# controller_board.net
KiCad netlist of a schematic drawn in EAGLE
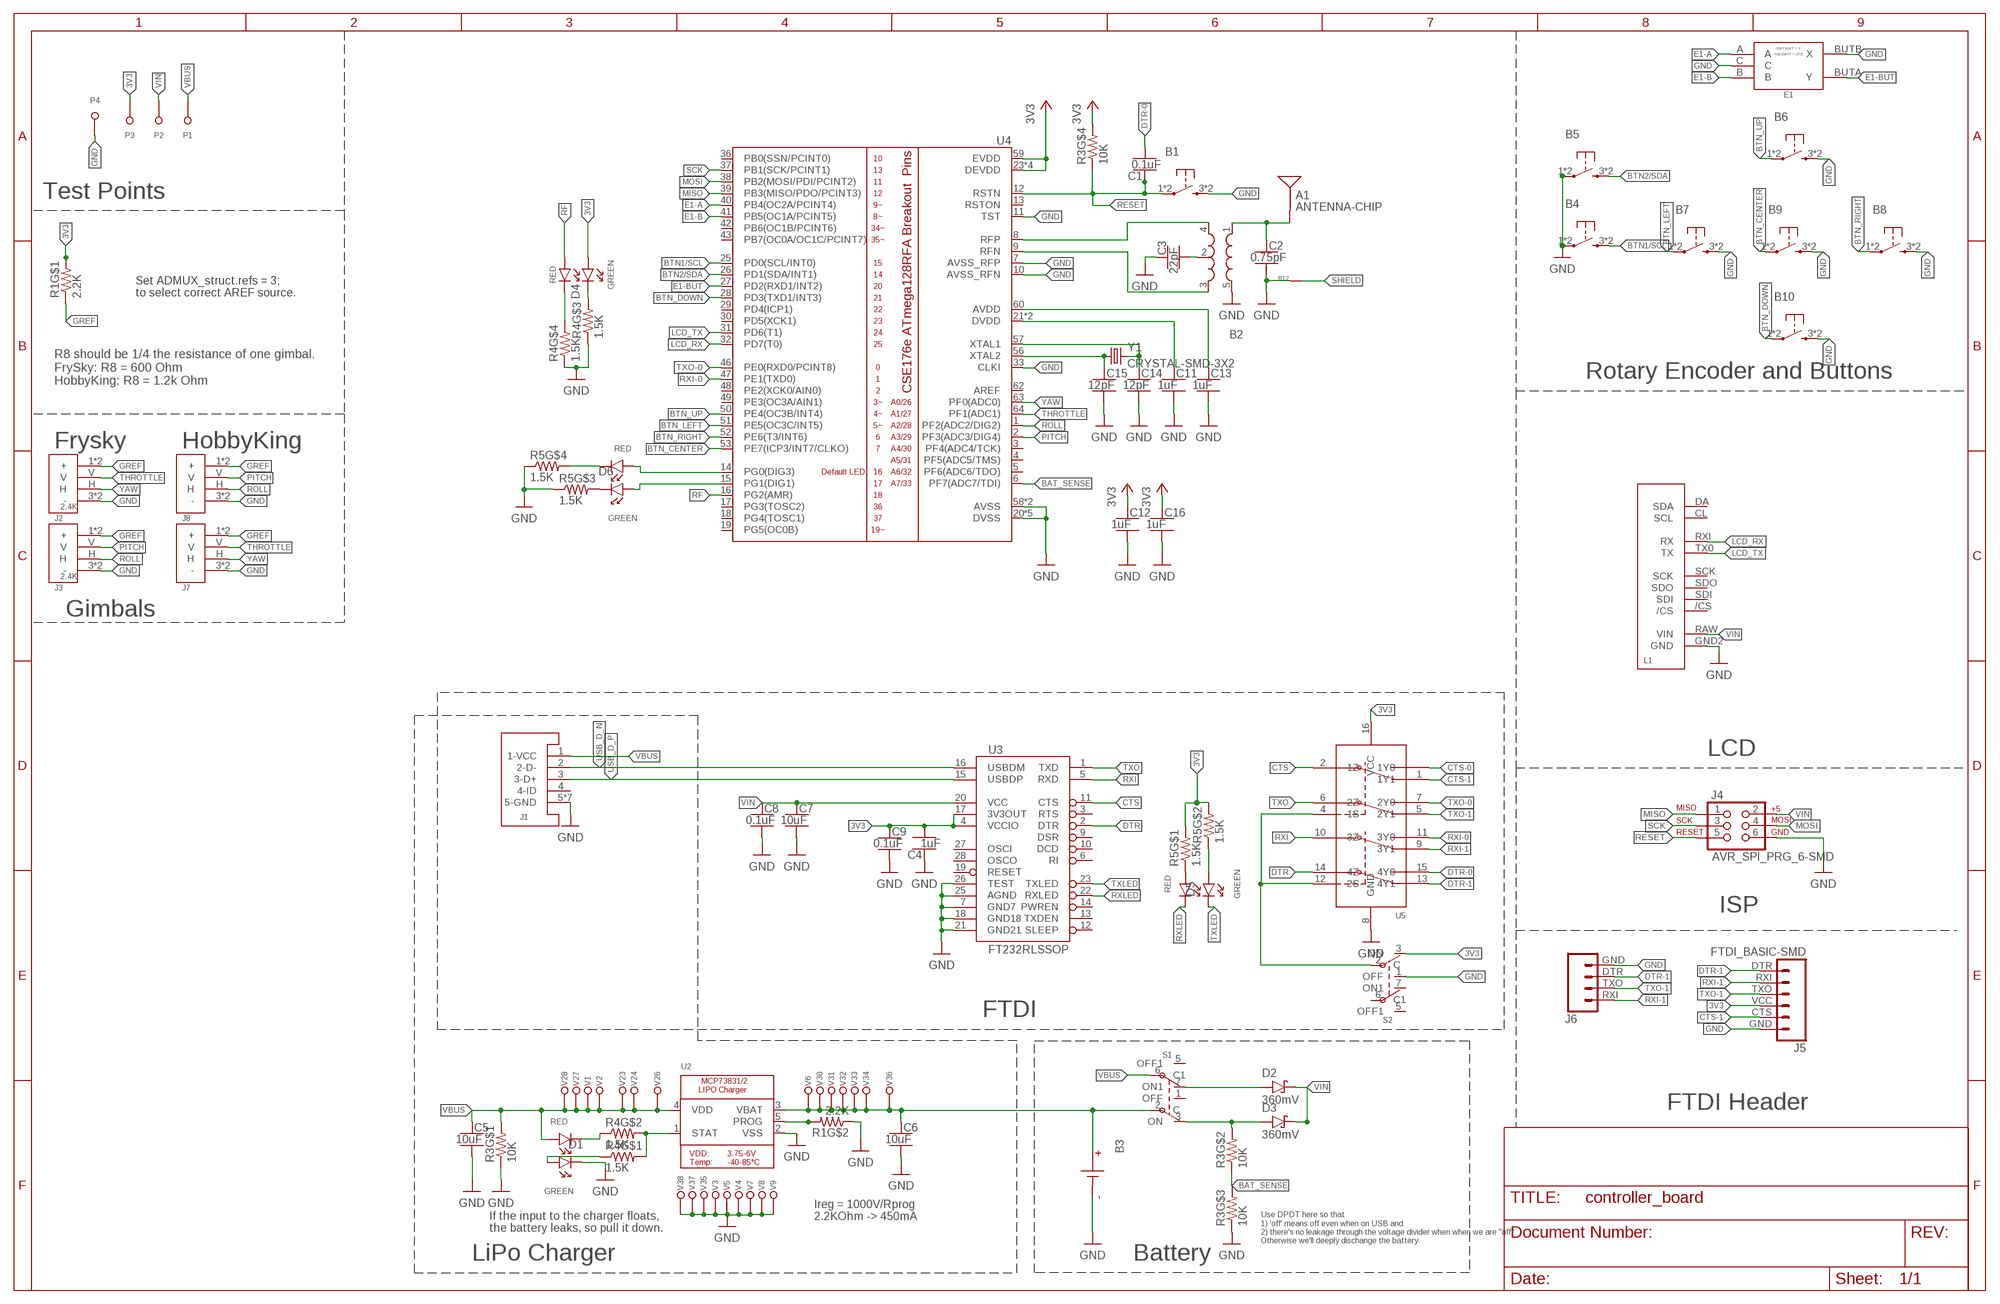
[diagram p0: schematic, sheet 1]

(export (version "E")
  (design (tool "Eeschema 10.0.6"))
  (components
    (comp (ref "A1")
      (value "ANTENNA-CHIP")
      (footprint "eagle-import:ANTENNA-CHIP")
      (fields (field (name "MFR") "Linx Technologies Inc.") (field (name "MPN") "ANT-2.45-CHP-T"))
      (libsource (lib "eagle-import") (part "ANTENNA-CHIP"))
    )
    (comp (ref "B1")
      (value "PUSHBUTTON_-4.5X4.5")
      (footprint "eagle-import:4.5MM_TACTILE_SWITCH_TL3305AF160QG")
      (fields (field (name "MFR") "E-Switch") (field (name "MPN") "TL3305AF160QG"))
      (libsource (lib "eagle-import") (part "PUSHBUTTON_-4.5X4.5"))
    )
    (comp (ref "B2")
      (value "BALUN0805")
      (footprint "eagle-import:BALUN")
      (fields (field (name "MFR") "Wurth Electronics Inc.") (field (name "MPN") "748421245"))
      (libsource (lib "eagle-import") (part "BALUN0805"))
    )
    (comp (ref "B3")
      (value "BATTERY-SMD")
      (footprint "eagle-import:MOLEX-BATTERY-CONNECTOR-SMD-51005-2P")
      (fields (field (name "MFR") "UNKNOWN"))
      (libsource (lib "eagle-import") (part "BATTERY-SMD"))
    )
    (comp (ref "B4")
      (value "PUSHBUTTON_-4.5X4.5")
      (footprint "eagle-import:4.5MM_TACTILE_SWITCH_TL3305AF160QG")
      (fields (field (name "MFR") "E-Switch") (field (name "MPN") "TL3305AF160QG"))
      (libsource (lib "eagle-import") (part "PUSHBUTTON_-4.5X4.5"))
    )
    (comp (ref "B5")
      (value "PUSHBUTTON_-4.5X4.5")
      (footprint "eagle-import:4.5MM_TACTILE_SWITCH_TL3305AF160QG")
      (fields (field (name "MFR") "E-Switch") (field (name "MPN") "TL3305AF160QG"))
      (libsource (lib "eagle-import") (part "PUSHBUTTON_-4.5X4.5"))
    )
    (comp (ref "B6")
      (value "PUSHBUTTON_-4.5X4.5")
      (footprint "eagle-import:4.5MM_TACTILE_SWITCH_TL3305AF160QG")
      (fields (field (name "MFR") "E-Switch") (field (name "MPN") "TL3305AF160QG"))
      (libsource (lib "eagle-import") (part "PUSHBUTTON_-4.5X4.5"))
    )
    (comp (ref "B7")
      (value "PUSHBUTTON_-4.5X4.5")
      (footprint "eagle-import:4.5MM_TACTILE_SWITCH_TL3305AF160QG")
      (fields (field (name "MFR") "E-Switch") (field (name "MPN") "TL3305AF160QG"))
      (libsource (lib "eagle-import") (part "PUSHBUTTON_-4.5X4.5"))
    )
    (comp (ref "B8")
      (value "PUSHBUTTON_-4.5X4.5")
      (footprint "eagle-import:4.5MM_TACTILE_SWITCH_TL3305AF160QG")
      (fields (field (name "MFR") "E-Switch") (field (name "MPN") "TL3305AF160QG"))
      (libsource (lib "eagle-import") (part "PUSHBUTTON_-4.5X4.5"))
    )
    (comp (ref "B9")
      (value "PUSHBUTTON_-4.5X4.5")
      (footprint "eagle-import:4.5MM_TACTILE_SWITCH_TL3305AF160QG")
      (fields (field (name "MFR") "E-Switch") (field (name "MPN") "TL3305AF160QG"))
      (libsource (lib "eagle-import") (part "PUSHBUTTON_-4.5X4.5"))
    )
    (comp (ref "B10")
      (value "PUSHBUTTON_-4.5X4.5")
      (footprint "eagle-import:4.5MM_TACTILE_SWITCH_TL3305AF160QG")
      (fields (field (name "MFR") "E-Switch") (field (name "MPN") "TL3305AF160QG"))
      (libsource (lib "eagle-import") (part "PUSHBUTTON_-4.5X4.5"))
    )
    (comp (ref "B12")
      (value "NET_BRIDGE")
      (footprint "eagle-import:NET_BRIDGE")
      (libsource (lib "eagle-import") (part "NET_BRIDGE"))
    )
    (comp (ref "C1")
      (value "0.1uF")
      (footprint "eagle-import:CAPC1608X100")
      (fields (field (name "MFR") "KEMET") (field (name "MPN") "C0603C104K8RACTU"))
      (libsource (lib "eagle-import") (part "CAPACITOR-NP_SMD-0603_CERAMIC-0.1UF"))
    )
    (comp (ref "C2")
      (value "0.75pF")
      (footprint "eagle-import:CAPC1608X100")
      (fields (field (name "MFR") "Yageo") (field (name "MPN") "CC0603BRNPO9BNR75"))
      (libsource (lib "eagle-import") (part "CAPACITOR-NP_SMD-0603_CERAMIC-0.75PF"))
    )
    (comp (ref "C3")
      (value "22pF")
      (footprint "eagle-import:CAPC1608X100")
      (fields (field (name "MFR") "AVX Corporation") (field (name "MPN") "06036A220KAT2A"))
      (libsource (lib "eagle-import") (part "CAPACITOR-NP_SMD-0603_CERAMIC-22PF"))
    )
    (comp (ref "C4")
      (value "1uF")
      (footprint "eagle-import:CAPC1608X100")
      (fields (field (name "MFR") "Samsung Electro-Mechanics") (field (name "MPN") "CL10A105KP8NNNC"))
      (libsource (lib "eagle-import") (part "CAPACITOR-NP_SMD-0603_CERAMIC-1UF"))
    )
    (comp (ref "C5")
      (value "10uF")
      (footprint "eagle-import:CAPC1608X100")
      (fields (field (name "MFR") "Samsung Electro-Mechanics") (field (name "MPN") "CL10A106MQ8NNNC"))
      (libsource (lib "eagle-import") (part "CAPACITOR-NP_SMD-0603_CERAMIC-10UF"))
    )
    (comp (ref "C6")
      (value "10uF")
      (footprint "eagle-import:CAPC1608X100")
      (fields (field (name "MFR") "Samsung Electro-Mechanics") (field (name "MPN") "CL10A106MQ8NNNC"))
      (libsource (lib "eagle-import") (part "CAPACITOR-NP_SMD-0603_CERAMIC-10UF"))
    )
    (comp (ref "C7")
      (value "10uF")
      (footprint "eagle-import:CAPC1608X100")
      (fields (field (name "MFR") "Samsung Electro-Mechanics") (field (name "MPN") "CL10A106MQ8NNNC"))
      (libsource (lib "eagle-import") (part "CAPACITOR-NP_SMD-0603_CERAMIC-10UF"))
    )
    (comp (ref "C8")
      (value "0.1uF")
      (footprint "eagle-import:CAPC1608X100")
      (fields (field (name "MFR") "KEMET") (field (name "MPN") "C0603C104K8RACTU"))
      (libsource (lib "eagle-import") (part "CAPACITOR-NP_SMD-0603_CERAMIC-0.1UF"))
    )
    (comp (ref "C9")
      (value "0.1uF")
      (footprint "eagle-import:CAPC1608X100")
      (fields (field (name "MFR") "KEMET") (field (name "MPN") "C0603C104K8RACTU"))
      (libsource (lib "eagle-import") (part "CAPACITOR-NP_SMD-0603_CERAMIC-0.1UF"))
    )
    (comp (ref "C11")
      (value "1uF")
      (footprint "eagle-import:CAPC1608X100")
      (fields (field (name "MFR") "Samsung Electro-Mechanics") (field (name "MPN") "CL10A105KP8NNNC"))
      (libsource (lib "eagle-import") (part "CAPACITOR-NP_SMD-0603_CERAMIC-1UF"))
    )
    (comp (ref "C12")
      (value "1uF")
      (footprint "eagle-import:CAPC1608X100")
      (fields (field (name "MFR") "Samsung Electro-Mechanics") (field (name "MPN") "CL10A105KP8NNNC"))
      (libsource (lib "eagle-import") (part "CAPACITOR-NP_SMD-0603_CERAMIC-1UF"))
    )
    (comp (ref "C13")
      (value "1uF")
      (footprint "eagle-import:CAPC1608X100")
      (fields (field (name "MFR") "Samsung Electro-Mechanics") (field (name "MPN") "CL10A105KP8NNNC"))
      (libsource (lib "eagle-import") (part "CAPACITOR-NP_SMD-0603_CERAMIC-1UF"))
    )
    (comp (ref "C14")
      (value "12pF")
      (footprint "eagle-import:CAPC1608X100")
      (fields (field (name "MFR") "Vishay Vitramon") (field (name "MPN") "VJ0603A120FXQCW1BC"))
      (libsource (lib "eagle-import") (part "CAPACITOR-NP_SMD-0603_CERAMIC-12PF"))
    )
    (comp (ref "C15")
      (value "12pF")
      (footprint "eagle-import:CAPC1608X100")
      (fields (field (name "MFR") "Vishay Vitramon") (field (name "MPN") "VJ0603A120FXQCW1BC"))
      (libsource (lib "eagle-import") (part "CAPACITOR-NP_SMD-0603_CERAMIC-12PF"))
    )
    (comp (ref "C16")
      (value "1uF")
      (footprint "eagle-import:CAPC1608X100")
      (fields (field (name "MFR") "Samsung Electro-Mechanics") (field (name "MPN") "CL10A105KP8NNNC"))
      (libsource (lib "eagle-import") (part "CAPACITOR-NP_SMD-0603_CERAMIC-1UF"))
    )
    (comp (ref "D1")
      (value "LED-2X-GREEN/RED-1.6X1.5MM")
      (footprint "eagle-import:LED-2X-LITE-ON-1.6MMX1.5MM")
      (fields
        (field (name "COLOR2") "GREEN")
        (field (name "COLOR1") "RED")
        (field (name "MFR") "Lite-On Inc.")
        (field (name "MPN") "LTST-C195TGKRKT")
      )
      (libsource (lib "eagle-import") (part "LED-2X-GREEN/RED-1.6X1.5MM"))
    )
    (comp (ref "D2")
      (value "360mV")
      (footprint "eagle-import:SODFL3516X96")
      (fields
        (field (name "MFR") "Toshiba Semiconductor and Storage")
        (field (name "MPN") "CRS08(TE85L,Q,M)")
      )
      (libsource (lib "eagle-import") (part "DIODE-SCHOTTKY_-SMD-SOD123"))
    )
    (comp (ref "D3")
      (value "360mV")
      (footprint "eagle-import:SODFL3516X96")
      (fields
        (field (name "MFR") "Toshiba Semiconductor and Storage")
        (field (name "MPN") "CRS08(TE85L,Q,M)")
      )
      (libsource (lib "eagle-import") (part "DIODE-SCHOTTKY_-SMD-SOD123"))
    )
    (comp (ref "D4")
      (value "LED-2X-GREEN/RED-1.6X1.5MM")
      (footprint "eagle-import:LED-2X-LITE-ON-1.6MMX1.5MM")
      (fields
        (field (name "COLOR2") "GREEN")
        (field (name "COLOR1") "RED")
        (field (name "MFR") "Lite-On Inc.")
        (field (name "MPN") "LTST-C195TGKRKT")
      )
      (libsource (lib "eagle-import") (part "LED-2X-GREEN/RED-1.6X1.5MM"))
    )
    (comp (ref "D5")
      (value "LED-2X-GREEN/RED-1.6X1.5MM")
      (footprint "eagle-import:LED-2X-LITE-ON-1.6MMX1.5MM")
      (fields
        (field (name "COLOR2") "GREEN")
        (field (name "COLOR1") "RED")
        (field (name "MFR") "Lite-On Inc.")
        (field (name "MPN") "LTST-C195TGKRKT")
      )
      (libsource (lib "eagle-import") (part "LED-2X-GREEN/RED-1.6X1.5MM"))
    )
    (comp (ref "D6")
      (value "LED-2X-GREEN/RED-1.6X1.5MM")
      (footprint "eagle-import:LED-2X-LITE-ON-1.6MMX1.5MM")
      (fields
        (field (name "COLOR2") "GREEN")
        (field (name "COLOR1") "RED")
        (field (name "MFR") "Lite-On Inc.")
        (field (name "MPN") "LTST-C195TGKRKT")
      )
      (libsource (lib "eagle-import") (part "LED-2X-GREEN/RED-1.6X1.5MM"))
    )
    (comp (ref "E1")
      (value "ROTARY-ENCODER-W/BUTTON-BOURNS-PEC12R-4217F")
      (footprint "eagle-import:BOURNS-PEC12R")
      (fields (field (name "DETENT") "Y") (field (name "HEIGHT") "17.5"))
      (libsource (lib "eagle-import") (part "ROTARY-ENCODER-W/BUTTON-BOURNS-PEC12R-4217F"))
    )
    (comp (ref "J1")
      (value "USB-MICROA-AMPHENOL-10118192-0001LF")
      (footprint "eagle-import:USB-MICROA-10118192-0001LF")
      (libsource (lib "eagle-import") (part "USB-MICROA-AMPHENOL-10118192-0001LF"))
    )
    (comp (ref "J2")
      (value "2.4K")
      (footprint "eagle-import:JST-13-PTH")
      (fields (field (name "MFR") "TE Connectivity AMP Connectors") (field (name "MPN") "1-1735446-2"))
      (libsource (lib "eagle-import") (part "FRSKY-GIMBAL-FRYSKY"))
    )
    (comp (ref "J3")
      (value "2.4K")
      (footprint "eagle-import:JST-13-PTH")
      (fields
        (field (name "MFR") "TE Connectivity AMP Connectors")
        (field (name "MPN") "1-1735446-2")
        (field (name "SPICEPREFIX") "E")
      )
      (libsource (lib "eagle-import") (part "FRSKY-GIMBAL-FRYSKY"))
    )
    (comp (ref "J4")
      (value "AVR_SPI_PRG_6-SMD")
      (footprint "eagle-import:2X3-SMD")
      (fields (field (name "MFR") "Amphenol ICC (FCI)") (field (name "MPN") "95278-101A06LF"))
      (libsource (lib "eagle-import") (part "AVR_SPI_PRG_6-SMD"))
    )
    (comp (ref "J5")
      (value "FTDI_BASIC-SMD")
      (footprint "eagle-import:FTDI-BASIC-SMD")
      (fields (field (name "MFR") "Harwin Inc.") (field (name "MPN") "M20-8890645"))
      (libsource (lib "eagle-import") (part "FTDI_BASIC-SMD"))
    )
    (comp (ref "J6")
      (value "FTDI-4PIN-RIGHT-ANGLE-SMD")
      (footprint "eagle-import:HEADER-2X2-0.1IN-MALE-RIGHT-ANGLE-SMD")
      (libsource (lib "eagle-import") (part "FTDI-4PIN-RIGHT-ANGLE-SMD"))
    )
    (comp (ref "J7")
      (value "FRSKY-GIMBAL-2X-SERVO-SMD")
      (footprint "eagle-import:2X-SERVO-SMD")
      (fields (field (name "MFR") "Harwin Inc.") (field (name "MPN") "M20-8890645"))
      (libsource (lib "eagle-import") (part "FRSKY-GIMBAL-2X-SERVO-SMD"))
    )
    (comp (ref "J8")
      (value "FRSKY-GIMBAL-2X-SERVO-SMD")
      (footprint "eagle-import:2X-SERVO-SMD")
      (fields (field (name "MFR") "Harwin Inc.") (field (name "MPN") "M20-8890645"))
      (libsource (lib "eagle-import") (part "FRSKY-GIMBAL-2X-SERVO-SMD"))
    )
    (comp (ref "L1")
      (value "SPARKFUN_SERLCD_SERIAL_REDUCED-SMD")
      (footprint "eagle-import:SPARKFUN_SERLCD_16X2_REDUCED_SMD")
      (libsource (lib "eagle-import") (part "SPARKFUN_SERLCD_SERIAL_REDUCED-SMD"))
    )
    (comp (ref "P1")
      (value "TEST-POINT")
      (footprint "eagle-import:TEST-POINT-KEYSTONE-5000")
      (fields (field (name "MFR") "Keystone Electronics") (field (name "MPN") "5001"))
      (libsource (lib "eagle-import") (part "TEST-POINT"))
    )
    (comp (ref "P2")
      (value "TEST-POINT")
      (footprint "eagle-import:TEST-POINT-KEYSTONE-5000")
      (fields (field (name "MFR") "Keystone Electronics") (field (name "MPN") "5001"))
      (libsource (lib "eagle-import") (part "TEST-POINT"))
    )
    (comp (ref "P3")
      (value "TEST-POINT")
      (footprint "eagle-import:TEST-POINT-KEYSTONE-5000")
      (fields (field (name "MFR") "Keystone Electronics") (field (name "MPN") "5001"))
      (libsource (lib "eagle-import") (part "TEST-POINT"))
    )
    (comp (ref "P4")
      (value "TEST-POINT")
      (footprint "eagle-import:TEST-POINT-KEYSTONE-5000")
      (fields (field (name "MFR") "Keystone Electronics") (field (name "MPN") "5001"))
      (libsource (lib "eagle-import") (part "TEST-POINT"))
    )
    (comp (ref "R1")
      (value "2.2K")
      (footprint "eagle-import:RESCAXS50P200X100X45-8")
      (libsource (lib "eagle-import") (part "RESISTOR-PACK-4X-2.2K"))
    )
    (comp (ref "R3")
      (value "10K")
      (footprint "eagle-import:RESCAXS50P200X100X45-8")
      (fields (field (name "MFR") "Panasonic Electronic Components") (field (name "MPN") "EXB-N8V103JX"))
      (libsource (lib "eagle-import") (part "RESISTOR-PACK-4X-10K"))
    )
    (comp (ref "R4")
      (value "1.5K")
      (footprint "eagle-import:RESCAXS50P200X100X45-8")
      (libsource (lib "eagle-import") (part "RESISTOR-PACK-4X-1.5K"))
    )
    (comp (ref "R5")
      (value "1.5K")
      (footprint "eagle-import:RESCAXS50P200X100X45-8")
      (libsource (lib "eagle-import") (part "RESISTOR-PACK-4X-1.5K"))
    )
    (comp (ref "S1")
      (value "SWITCH-DPDT-300MA-6V-SMD")
      (footprint "eagle-import:JS202011JCQN")
      (libsource (lib "eagle-import") (part "SWITCH-DPDT-300MA-6V-SMD"))
    )
    (comp (ref "S2")
      (value "SWITCH-DPDT-300MA-6V-SMD")
      (footprint "eagle-import:JS202011JCQN")
      (libsource (lib "eagle-import") (part "SWITCH-DPDT-300MA-6V-SMD"))
    )
    (comp (ref "U2")
      (value "MCP73831T-2ACI/OT")
      (footprint "eagle-import:SOT23-5")
      (fields (field (name "MFR") "Microchip Technology"))
      (libsource (lib "eagle-import") (part "MCP73831/2"))
    )
    (comp (ref "U3")
      (value "FT232RLSSOP")
      (footprint "eagle-import:SSOP28DB")
      (libsource (lib "eagle-import") (part "FT232RLSSOP"))
    )
    (comp (ref "U4")
      (value "ATMEGA128RFA1")
      (footprint "eagle-import:QFN-64")
      (fields (field (name "MFR") "Microchip Technology") (field (name "MPN") "ATMEGA128RFA1-ZU"))
      (libsource (lib "eagle-import") (part "ATMEGA128RFA1"))
    )
    (comp (ref "U5")
      (value "DPDT-X2")
      (footprint "eagle-import:SOP65P640X110-16")
      (fields (field (name "MFR") "NXP USA Inc.") (field (name "MPN") "NX3L2467PW,118"))
      (libsource (lib "eagle-import") (part "DPDT-X2"))
    )
    (comp (ref "V1")
      (value "LOCKED-VIA-0.2")
      (footprint "eagle-import:VIA-0.2MM")
      (libsource (lib "eagle-import") (part "LOCKED-VIA-0.2"))
    )
    (comp (ref "V2")
      (value "LOCKED-VIA-0.2")
      (footprint "eagle-import:VIA-0.2MM")
      (libsource (lib "eagle-import") (part "LOCKED-VIA-0.2"))
    )
    (comp (ref "V3")
      (value "LOCKED-VIA-0.2")
      (footprint "eagle-import:VIA-0.2MM")
      (libsource (lib "eagle-import") (part "LOCKED-VIA-0.2"))
    )
    (comp (ref "V4")
      (value "LOCKED-VIA-0.2")
      (footprint "eagle-import:VIA-0.2MM")
      (libsource (lib "eagle-import") (part "LOCKED-VIA-0.2"))
    )
    (comp (ref "V5")
      (value "LOCKED-VIA-0.2")
      (footprint "eagle-import:VIA-0.2MM")
      (libsource (lib "eagle-import") (part "LOCKED-VIA-0.2"))
    )
    (comp (ref "V6")
      (value "LOCKED-VIA-0.2")
      (footprint "eagle-import:VIA-0.2MM")
      (libsource (lib "eagle-import") (part "LOCKED-VIA-0.2"))
    )
    (comp (ref "V7")
      (value "LOCKED-VIA-0.2")
      (footprint "eagle-import:VIA-0.2MM")
      (libsource (lib "eagle-import") (part "LOCKED-VIA-0.2"))
    )
    (comp (ref "V8")
      (value "LOCKED-VIA-0.2")
      (footprint "eagle-import:VIA-0.2MM")
      (libsource (lib "eagle-import") (part "LOCKED-VIA-0.2"))
    )
    (comp (ref "V9")
      (value "LOCKED-VIA-0.2")
      (footprint "eagle-import:VIA-0.2MM")
      (libsource (lib "eagle-import") (part "LOCKED-VIA-0.2"))
    )
    (comp (ref "V23")
      (value "LOCKED-VIA-0.2")
      (footprint "eagle-import:VIA-0.2MM")
      (libsource (lib "eagle-import") (part "LOCKED-VIA-0.2"))
    )
    (comp (ref "V24")
      (value "LOCKED-VIA-0.2")
      (footprint "eagle-import:VIA-0.2MM")
      (libsource (lib "eagle-import") (part "LOCKED-VIA-0.2"))
    )
    (comp (ref "V26")
      (value "LOCKED-VIA-0.2")
      (footprint "eagle-import:VIA-0.2MM")
      (libsource (lib "eagle-import") (part "LOCKED-VIA-0.2"))
    )
    (comp (ref "V27")
      (value "LOCKED-VIA-0.2")
      (footprint "eagle-import:VIA-0.2MM")
      (libsource (lib "eagle-import") (part "LOCKED-VIA-0.2"))
    )
    (comp (ref "V28")
      (value "LOCKED-VIA-0.2")
      (footprint "eagle-import:VIA-0.2MM")
      (libsource (lib "eagle-import") (part "LOCKED-VIA-0.2"))
    )
    (comp (ref "V30")
      (value "LOCKED-VIA-0.2")
      (footprint "eagle-import:VIA-0.2MM")
      (libsource (lib "eagle-import") (part "LOCKED-VIA-0.2"))
    )
    (comp (ref "V31")
      (value "LOCKED-VIA-0.2")
      (footprint "eagle-import:VIA-0.2MM")
      (libsource (lib "eagle-import") (part "LOCKED-VIA-0.2"))
    )
    (comp (ref "V32")
      (value "LOCKED-VIA-0.2")
      (footprint "eagle-import:VIA-0.2MM")
      (libsource (lib "eagle-import") (part "LOCKED-VIA-0.2"))
    )
    (comp (ref "V33")
      (value "LOCKED-VIA-0.2")
      (footprint "eagle-import:VIA-0.2MM")
      (libsource (lib "eagle-import") (part "LOCKED-VIA-0.2"))
    )
    (comp (ref "V34")
      (value "LOCKED-VIA-0.2")
      (footprint "eagle-import:VIA-0.2MM")
      (libsource (lib "eagle-import") (part "LOCKED-VIA-0.2"))
    )
    (comp (ref "V35")
      (value "LOCKED-VIA-0.2")
      (footprint "eagle-import:VIA-0.2MM")
      (libsource (lib "eagle-import") (part "LOCKED-VIA-0.2"))
    )
    (comp (ref "V36")
      (value "LOCKED-VIA-0.2")
      (footprint "eagle-import:VIA-0.2MM")
      (libsource (lib "eagle-import") (part "LOCKED-VIA-0.2"))
    )
    (comp (ref "V37")
      (value "LOCKED-VIA-0.2")
      (footprint "eagle-import:VIA-0.2MM")
      (libsource (lib "eagle-import") (part "LOCKED-VIA-0.2"))
    )
    (comp (ref "V38")
      (value "LOCKED-VIA-0.2")
      (footprint "eagle-import:VIA-0.2MM")
      (libsource (lib "eagle-import") (part "LOCKED-VIA-0.2"))
    )
    (comp (ref "Y1")
      (value "CRYSTAL-SMD-3X2")
      (footprint "eagle-import:OSCCC320X250X85")
      (fields (field (name "MFR") "Abracon LLC") (field (name "MPN") "ABM8-16.000MHZ-B2-T"))
      (libsource (lib "eagle-import") (part "CRYSTAL-SMD-3X2"))
    )
  )
  (nets
    (net (code "1") (name "3V3") (class "Default")
      (node (ref "C12") (pin "1") (pinfunction "1_1") (pintype "passive"))
      (node (ref "C16") (pin "1") (pinfunction "1_1") (pintype "passive"))
      (node (ref "C4") (pin "2") (pinfunction "2_2") (pintype "passive"))
      (node (ref "C9") (pin "1") (pinfunction "1_1") (pintype "passive"))
      (node (ref "D4") (pin "A1") (pinfunction "A1_A1") (pintype "passive"))
      (node (ref "J5") (pin "VCC") (pinfunction "4_VCC") (pintype "passive"))
      (node (ref "P3") (pin "T") (pinfunction "T_T") (pintype "bidirectional"))
      (node (ref "R1") (pin "5") (pinfunction "2_5") (pintype "passive"))
      (node (ref "R3") (pin "8") (pinfunction "2_8") (pintype "passive"))
      (node (ref "R5") (pin "5") (pinfunction "2_5") (pintype "passive"))
      (node (ref "R5") (pin "6") (pinfunction "2_6") (pintype "passive"))
      (node (ref "S2") (pin "3") (pinfunction "ON_3") (pintype "bidirectional"))
      (node (ref "U3") (pin "17") (pinfunction "3V3OUT_17") (pintype "output"))
      (node (ref "U3") (pin "4") (pinfunction "VCCIO_4") (pintype "power_in"))
      (node (ref "U4") (pin "23") (pinfunction "DEVDD_23") (pintype "bidirectional"))
      (node (ref "U4") (pin "34") (pinfunction "DEVDD_34") (pintype "bidirectional"))
      (node (ref "U4") (pin "44") (pinfunction "DEVDD_44") (pintype "bidirectional"))
      (node (ref "U4") (pin "54") (pinfunction "DEVDD_54") (pintype "bidirectional"))
      (node (ref "U4") (pin "59") (pinfunction "EVDD_59") (pintype "bidirectional"))
      (node (ref "U5") (pin "16") (pinfunction "VCC_16") (pintype "bidirectional"))
    )
    (net (code "2") (name "BAT_SENSE") (class "Default")
      (node (ref "R3") (pin "3") (pinfunction "1_3") (pintype "passive"))
      (node (ref "R3") (pin "7") (pinfunction "2_7") (pintype "passive"))
      (node (ref "U4") (pin "6") (pinfunction "PF7(ADC7/TDI)_6") (pintype "bidirectional"))
    )
    (net (code "3") (name "BTN1{slash}SCL") (class "Default")
      (node (ref "B4") (pin "3") (pinfunction "2_3") (pintype "passive"))
      (node (ref "B4") (pin "4") (pinfunction "2_4") (pintype "passive"))
      (node (ref "U4") (pin "25") (pinfunction "PD0(SCL/INT0)_25") (pintype "bidirectional"))
    )
    (net (code "4") (name "BTN2{slash}SDA") (class "Default")
      (node (ref "B5") (pin "3") (pinfunction "2_3") (pintype "passive"))
      (node (ref "B5") (pin "4") (pinfunction "2_4") (pintype "passive"))
      (node (ref "U4") (pin "26") (pinfunction "PD1(SDA/INT1)_26") (pintype "bidirectional"))
    )
    (net (code "5") (name "BTN_CENTER") (class "Default")
      (node (ref "B9") (pin "1") (pinfunction "1_1") (pintype "passive"))
      (node (ref "B9") (pin "2") (pinfunction "1_2") (pintype "passive"))
      (node (ref "U4") (pin "53") (pinfunction "PE7(ICP3/INT7/CLKO)_53") (pintype "bidirectional"))
    )
    (net (code "6") (name "BTN_DOWN") (class "Default")
      (node (ref "B10") (pin "1") (pinfunction "1_1") (pintype "passive"))
      (node (ref "B10") (pin "2") (pinfunction "1_2") (pintype "passive"))
      (node (ref "U4") (pin "28") (pinfunction "PD3(TXD1/INT3)_28") (pintype "bidirectional"))
    )
    (net (code "7") (name "BTN_LEFT") (class "Default")
      (node (ref "B7") (pin "1") (pinfunction "1_1") (pintype "passive"))
      (node (ref "B7") (pin "2") (pinfunction "1_2") (pintype "passive"))
      (node (ref "U4") (pin "51") (pinfunction "PE5(OC3C/INT5)_51") (pintype "bidirectional"))
    )
    (net (code "8") (name "BTN_RIGHT") (class "Default")
      (node (ref "B8") (pin "1") (pinfunction "1_1") (pintype "passive"))
      (node (ref "B8") (pin "2") (pinfunction "1_2") (pintype "passive"))
      (node (ref "U4") (pin "52") (pinfunction "PE6(T3/INT6)_52") (pintype "bidirectional"))
    )
    (net (code "9") (name "BTN_UP") (class "Default")
      (node (ref "B6") (pin "1") (pinfunction "1_1") (pintype "passive"))
      (node (ref "B6") (pin "2") (pinfunction "1_2") (pintype "passive"))
      (node (ref "U4") (pin "50") (pinfunction "PE4(OC3B/INT4)_50") (pintype "bidirectional"))
    )
    (net (code "10") (name "CTS") (class "Default")
      (node (ref "U3") (pin "11") (pinfunction "CTS_11") (pintype "input"))
      (node (ref "U5") (pin "2") (pinfunction "1Z_2") (pintype "bidirectional"))
    )
    (net (code "11") (name "CTS-0") (class "Default")
      (node (ref "U5") (pin "3") (pinfunction "1Y0_3") (pintype "bidirectional"))
    )
    (net (code "12") (name "CTS-1") (class "Default")
      (node (ref "J5") (pin "CTS") (pinfunction "5_CTS") (pintype "passive"))
      (node (ref "U5") (pin "1") (pinfunction "1Y1_1") (pintype "bidirectional"))
    )
    (net (code "13") (name "DTR") (class "Default")
      (node (ref "U3") (pin "2") (pinfunction "DTR_2") (pintype "output"))
      (node (ref "U5") (pin "14") (pinfunction "4Z_14") (pintype "bidirectional"))
    )
    (net (code "14") (name "DTR-0") (class "Default")
      (node (ref "C1") (pin "2") (pinfunction "2_2") (pintype "passive"))
      (node (ref "U5") (pin "15") (pinfunction "4Y0_15") (pintype "bidirectional"))
    )
    (net (code "15") (name "DTR-1") (class "Default")
      (node (ref "J5") (pin "DTR") (pinfunction "1_DTR") (pintype "passive"))
      (node (ref "J6") (pin "DTR") (pinfunction "3_DTR") (pintype "bidirectional"))
      (node (ref "U5") (pin "13") (pinfunction "4Y1_13") (pintype "bidirectional"))
    )
    (net (code "16") (name "E1-A") (class "Default")
      (node (ref "E1") (pin "A") (pinfunction "A_A") (pintype "bidirectional"))
      (node (ref "U4") (pin "40") (pinfunction "PB4(OC2A/PCINT4)_40") (pintype "bidirectional"))
    )
    (net (code "17") (name "E1-B") (class "Default")
      (node (ref "E1") (pin "B") (pinfunction "B_B") (pintype "bidirectional"))
      (node (ref "U4") (pin "41") (pinfunction "PB5(OC1A/PCINT5)_41") (pintype "bidirectional"))
    )
    (net (code "18") (name "E1-BUT") (class "Default")
      (node (ref "E1") (pin "BUTA") (pinfunction "Y_BUTA") (pintype "bidirectional"))
      (node (ref "U4") (pin "27") (pinfunction "PD2(RXD1/INT2)_27") (pintype "bidirectional"))
    )
    (net (code "19") (name "GND") (class "Default")
      (node (ref "B1") (pin "3") (pinfunction "2_3") (pintype "passive"))
      (node (ref "B1") (pin "4") (pinfunction "2_4") (pintype "passive"))
      (node (ref "B10") (pin "3") (pinfunction "2_3") (pintype "passive"))
      (node (ref "B10") (pin "4") (pinfunction "2_4") (pintype "passive"))
      (node (ref "B12") (pin "P1") (pinfunction "P1_P1") (pintype "bidirectional"))
      (node (ref "B2") (pin "5") (pinfunction "GND_5") (pintype "bidirectional"))
      (node (ref "B3") (pin "G") (pinfunction "N_G") (pintype "bidirectional"))
      (node (ref "B3") (pin "G2") (pinfunction "N_G2") (pintype "bidirectional"))
      (node (ref "B3") (pin "G3") (pinfunction "N_G3") (pintype "bidirectional"))
      (node (ref "B4") (pin "1") (pinfunction "1_1") (pintype "passive"))
      (node (ref "B4") (pin "2") (pinfunction "1_2") (pintype "passive"))
      (node (ref "B5") (pin "1") (pinfunction "1_1") (pintype "passive"))
      (node (ref "B5") (pin "2") (pinfunction "1_2") (pintype "passive"))
      (node (ref "B6") (pin "3") (pinfunction "2_3") (pintype "passive"))
      (node (ref "B6") (pin "4") (pinfunction "2_4") (pintype "passive"))
      (node (ref "B7") (pin "3") (pinfunction "2_3") (pintype "passive"))
      (node (ref "B7") (pin "4") (pinfunction "2_4") (pintype "passive"))
      (node (ref "B8") (pin "3") (pinfunction "2_3") (pintype "passive"))
      (node (ref "B8") (pin "4") (pinfunction "2_4") (pintype "passive"))
      (node (ref "B9") (pin "3") (pinfunction "2_3") (pintype "passive"))
      (node (ref "B9") (pin "4") (pinfunction "2_4") (pintype "passive"))
      (node (ref "C11") (pin "2") (pinfunction "2_2") (pintype "passive"))
      (node (ref "C12") (pin "2") (pinfunction "2_2") (pintype "passive"))
      (node (ref "C13") (pin "2") (pinfunction "2_2") (pintype "passive"))
      (node (ref "C14") (pin "2") (pinfunction "2_2") (pintype "passive"))
      (node (ref "C15") (pin "2") (pinfunction "2_2") (pintype "passive"))
      (node (ref "C16") (pin "2") (pinfunction "2_2") (pintype "passive"))
      (node (ref "C2") (pin "2") (pinfunction "2_2") (pintype "passive"))
      (node (ref "C3") (pin "1") (pinfunction "1_1") (pintype "passive"))
      (node (ref "C4") (pin "1") (pinfunction "1_1") (pintype "passive"))
      (node (ref "C5") (pin "2") (pinfunction "2_2") (pintype "passive"))
      (node (ref "C6") (pin "2") (pinfunction "2_2") (pintype "passive"))
      (node (ref "C7") (pin "2") (pinfunction "2_2") (pintype "passive"))
      (node (ref "C8") (pin "2") (pinfunction "2_2") (pintype "passive"))
      (node (ref "C9") (pin "2") (pinfunction "2_2") (pintype "passive"))
      (node (ref "D1") (pin "C1") (pinfunction "C1_C1") (pintype "passive"))
      (node (ref "E1") (pin "BUTB") (pinfunction "X_BUTB") (pintype "bidirectional"))
      (node (ref "E1") (pin "C") (pinfunction "C_C") (pintype "bidirectional"))
      (node (ref "J1") (pin "10") (pinfunction "5-GND_10") (pintype "bidirectional"))
      (node (ref "J1") (pin "11") (pinfunction "5-GND_11") (pintype "bidirectional"))
      (node (ref "J1") (pin "5") (pinfunction "5-GND_5") (pintype "bidirectional"))
      (node (ref "J1") (pin "6") (pinfunction "5-GND_6") (pintype "bidirectional"))
      (node (ref "J1") (pin "7") (pinfunction "5-GND_7") (pintype "bidirectional"))
      (node (ref "J1") (pin "8") (pinfunction "5-GND_8") (pintype "bidirectional"))
      (node (ref "J1") (pin "9") (pinfunction "5-GND_9") (pintype "bidirectional"))
      (node (ref "J2") (pin "3") (pinfunction "-_3") (pintype "bidirectional"))
      (node (ref "J2") (pin "6") (pinfunction "-_6") (pintype "bidirectional"))
      (node (ref "J3") (pin "3") (pinfunction "-_3") (pintype "bidirectional"))
      (node (ref "J3") (pin "6") (pinfunction "-_6") (pintype "bidirectional"))
      (node (ref "J4") (pin "6") (pinfunction "6_6") (pintype "passive"))
      (node (ref "J5") (pin "GND") (pinfunction "6_GND") (pintype "passive"))
      (node (ref "J6") (pin "GND") (pinfunction "4_GND") (pintype "bidirectional"))
      (node (ref "J7") (pin "3") (pinfunction "-_3") (pintype "bidirectional"))
      (node (ref "J7") (pin "6") (pinfunction "-_6") (pintype "bidirectional"))
      (node (ref "J8") (pin "3") (pinfunction "-_3") (pintype "bidirectional"))
      (node (ref "J8") (pin "6") (pinfunction "-_6") (pintype "bidirectional"))
      (node (ref "L1") (pin "GND2") (pinfunction "GND_GND2") (pintype "bidirectional"))
      (node (ref "P4") (pin "T") (pinfunction "T_T") (pintype "bidirectional"))
      (node (ref "R1") (pin "3") (pinfunction "1_3") (pintype "passive"))
      (node (ref "R3") (pin "2") (pinfunction "1_2") (pintype "passive"))
      (node (ref "R3") (pin "4") (pinfunction "1_4") (pintype "passive"))
      (node (ref "R4") (pin "1") (pinfunction "1_1") (pintype "passive"))
      (node (ref "R4") (pin "2") (pinfunction "1_2") (pintype "passive"))
      (node (ref "R5") (pin "1") (pinfunction "1_1") (pintype "passive"))
      (node (ref "R5") (pin "2") (pinfunction "1_2") (pintype "passive"))
      (node (ref "S2") (pin "1") (pinfunction "OFF_1") (pintype "bidirectional"))
      (node (ref "U2") (pin "2") (pinfunction "VSS_2") (pintype "power_in"))
      (node (ref "U3") (pin "18") (pinfunction "GND18_18") (pintype "power_in"))
      (node (ref "U3") (pin "21") (pinfunction "GND21_21") (pintype "power_in"))
      (node (ref "U3") (pin "25") (pinfunction "AGND_25") (pintype "power_in"))
      (node (ref "U3") (pin "26") (pinfunction "TEST_26") (pintype "input"))
      (node (ref "U3") (pin "7") (pinfunction "GND7_7") (pintype "power_in"))
      (node (ref "U4") (pin "10") (pinfunction "AVSS_RFN_10") (pintype "bidirectional"))
      (node (ref "U4") (pin "11") (pinfunction "TST_11") (pintype "bidirectional"))
      (node (ref "U4") (pin "20") (pinfunction "DVSS_20") (pintype "bidirectional"))
      (node (ref "U4") (pin "24") (pinfunction "DVSS_24") (pintype "bidirectional"))
      (node (ref "U4") (pin "33") (pinfunction "CLKI_33") (pintype "bidirectional"))
      (node (ref "U4") (pin "35") (pinfunction "DVSS_35") (pintype "bidirectional"))
      (node (ref "U4") (pin "45") (pinfunction "DVSS_45") (pintype "bidirectional"))
      (node (ref "U4") (pin "55") (pinfunction "DVSS_55") (pintype "bidirectional"))
      (node (ref "U4") (pin "58") (pinfunction "AVSS_58") (pintype "bidirectional"))
      (node (ref "U4") (pin "61") (pinfunction "AVSS_61") (pintype "bidirectional"))
      (node (ref "U4") (pin "7") (pinfunction "AVSS_RFP_7") (pintype "bidirectional"))
      (node (ref "U5") (pin "8") (pinfunction "GND_8") (pintype "bidirectional"))
      (node (ref "V3") (pin "P1") (pinfunction "N_P1") (pintype "bidirectional"))
      (node (ref "V35") (pin "P1") (pinfunction "N_P1") (pintype "bidirectional"))
      (node (ref "V37") (pin "P1") (pinfunction "N_P1") (pintype "bidirectional"))
      (node (ref "V38") (pin "P1") (pinfunction "N_P1") (pintype "bidirectional"))
      (node (ref "V4") (pin "P1") (pinfunction "N_P1") (pintype "bidirectional"))
      (node (ref "V5") (pin "P1") (pinfunction "N_P1") (pintype "bidirectional"))
      (node (ref "V7") (pin "P1") (pinfunction "N_P1") (pintype "bidirectional"))
      (node (ref "V8") (pin "P1") (pinfunction "N_P1") (pintype "bidirectional"))
      (node (ref "V9") (pin "P1") (pinfunction "N_P1") (pintype "bidirectional"))
    )
    (net (code "20") (name "GREF") (class "Default")
      (node (ref "J2") (pin "1") (pinfunction "+_1") (pintype "bidirectional"))
      (node (ref "J2") (pin "4") (pinfunction "+_4") (pintype "bidirectional"))
      (node (ref "J3") (pin "1") (pinfunction "+_1") (pintype "bidirectional"))
      (node (ref "J3") (pin "4") (pinfunction "+_4") (pintype "bidirectional"))
      (node (ref "J7") (pin "1") (pinfunction "+_1") (pintype "bidirectional"))
      (node (ref "J7") (pin "4") (pinfunction "+_4") (pintype "bidirectional"))
      (node (ref "J8") (pin "1") (pinfunction "+_1") (pintype "bidirectional"))
      (node (ref "J8") (pin "4") (pinfunction "+_4") (pintype "bidirectional"))
      (node (ref "R1") (pin "4") (pinfunction "1_4") (pintype "passive"))
    )
    (net (code "21") (name "LCD_RX") (class "Default")
      (node (ref "L1") (pin "RXI") (pinfunction "RX_RXI") (pintype "bidirectional"))
      (node (ref "U4") (pin "32") (pinfunction "PD7(T0)_32") (pintype "bidirectional"))
    )
    (net (code "22") (name "LCD_TX") (class "Default")
      (node (ref "L1") (pin "TX0") (pinfunction "TX_TX0") (pintype "bidirectional"))
      (node (ref "U4") (pin "31") (pinfunction "PD6(T1)_31") (pintype "bidirectional"))
    )
    (net (code "23") (name "MISO") (class "Default")
      (node (ref "J4") (pin "1") (pinfunction "1_1") (pintype "passive"))
      (node (ref "U4") (pin "39") (pinfunction "PB3(MISO/PDO/PCINT3)_39") (pintype "bidirectional"))
    )
    (net (code "24") (name "MOSI") (class "Default")
      (node (ref "J4") (pin "4") (pinfunction "4_4") (pintype "passive"))
      (node (ref "U4") (pin "38") (pinfunction "PB2(MOSI/PDI/PCINT2)_38") (pintype "bidirectional"))
    )
    (net (code "25") (name "Net-(A1-SIGNAL)") (class "Default")
      (node (ref "A1") (pin "FEED") (pinfunction "SIGNAL_FEED") (pintype "bidirectional"))
      (node (ref "B2") (pin "1") (pinfunction "IN_1") (pintype "bidirectional"))
      (node (ref "C2") (pin "1") (pinfunction "1_1") (pintype "passive"))
    )
    (net (code "26") (name "Net-(B2-GND-Pad2)") (class "Default")
      (node (ref "B2") (pin "2") (pinfunction "GND_2") (pintype "bidirectional"))
      (node (ref "C3") (pin "2") (pinfunction "2_2") (pintype "passive"))
    )
    (net (code "27") (name "Net-(B2-OUT1)") (class "Default")
      (node (ref "B2") (pin "4") (pinfunction "OUT1_4") (pintype "bidirectional"))
      (node (ref "U4") (pin "8") (pinfunction "RFP_8") (pintype "bidirectional"))
    )
    (net (code "28") (name "Net-(B2-OUT2)") (class "Default")
      (node (ref "B2") (pin "3") (pinfunction "OUT2_3") (pintype "bidirectional"))
      (node (ref "U4") (pin "9") (pinfunction "RFN_9") (pintype "bidirectional"))
    )
    (net (code "29") (name "Net-(C11-Pad1)") (class "Default")
      (node (ref "C11") (pin "1") (pinfunction "1_1") (pintype "passive"))
      (node (ref "U4") (pin "21") (pinfunction "DVDD_21") (pintype "bidirectional"))
      (node (ref "U4") (pin "22") (pinfunction "DVDD_22") (pintype "bidirectional"))
    )
    (net (code "30") (name "Net-(D2-A)") (class "Default")
      (node (ref "D2") (pin "2") (pinfunction "A_2") (pintype "passive"))
      (node (ref "S1") (pin "7") (pinfunction "ON1_7") (pintype "bidirectional"))
    )
    (net (code "31") (name "Net-(D3-A)") (class "Default")
      (node (ref "D3") (pin "2") (pinfunction "A_2") (pintype "passive"))
      (node (ref "R3") (pin "6") (pinfunction "2_6") (pintype "passive"))
      (node (ref "S1") (pin "3") (pinfunction "ON_3") (pintype "bidirectional"))
    )
    (net (code "32") (name "Net-(R1B-2)") (class "Default")
      (node (ref "R1") (pin "6") (pinfunction "2_6") (pintype "passive"))
      (node (ref "U2") (pin "5") (pinfunction "PROG_5") (pintype "input"))
    )
    (net (code "33") (name "Net-(R4A-1)") (class "Default")
      (node (ref "D1") (pin "A1") (pinfunction "A1_A1") (pintype "passive"))
      (node (ref "R4") (pin "4") (pinfunction "1_4") (pintype "passive"))
    )
    (net (code "34") (name "Net-(R4A-2)") (class "Default")
      (node (ref "R4") (pin "5") (pinfunction "2_5") (pintype "passive"))
      (node (ref "R4") (pin "6") (pinfunction "2_6") (pintype "passive"))
      (node (ref "U2") (pin "1") (pinfunction "STAT_1") (pintype "output"))
    )
    (net (code "35") (name "Net-(R4B-1)") (class "Default")
      (node (ref "D1") (pin "C2") (pinfunction "C2_C2") (pintype "passive"))
      (node (ref "R4") (pin "3") (pinfunction "1_3") (pintype "passive"))
    )
    (net (code "36") (name "Net-(R4C-2)") (class "Default")
      (node (ref "D4") (pin "C1") (pinfunction "C1_C1") (pintype "passive"))
      (node (ref "R4") (pin "7") (pinfunction "2_7") (pintype "passive"))
    )
    (net (code "37") (name "Net-(R4D-2)") (class "Default")
      (node (ref "D4") (pin "C2") (pinfunction "C2_C2") (pintype "passive"))
      (node (ref "R4") (pin "8") (pinfunction "2_8") (pintype "passive"))
    )
    (net (code "38") (name "Net-(R5A-1)") (class "Default")
      (node (ref "D5") (pin "A2") (pinfunction "A2_A2") (pintype "passive"))
      (node (ref "R5") (pin "4") (pinfunction "1_4") (pintype "passive"))
    )
    (net (code "39") (name "Net-(R5B-1)") (class "Default")
      (node (ref "D5") (pin "A1") (pinfunction "A1_A1") (pintype "passive"))
      (node (ref "R5") (pin "3") (pinfunction "1_3") (pintype "passive"))
    )
    (net (code "40") (name "Net-(R5C-2)") (class "Default")
      (node (ref "D6") (pin "C1") (pinfunction "C1_C1") (pintype "passive"))
      (node (ref "R5") (pin "7") (pinfunction "2_7") (pintype "passive"))
    )
    (net (code "41") (name "Net-(R5D-2)") (class "Default")
      (node (ref "D6") (pin "C2") (pinfunction "C2_C2") (pintype "passive"))
      (node (ref "R5") (pin "8") (pinfunction "2_8") (pintype "passive"))
    )
    (net (code "42") (name "Net-(S1-C)") (class "Default")
      (node (ref "B3") (pin "P") (pinfunction "P_P") (pintype "bidirectional"))
      (node (ref "C6") (pin "1") (pinfunction "1_1") (pintype "passive"))
      (node (ref "S1") (pin "2") (pinfunction "C_2") (pintype "bidirectional"))
      (node (ref "U2") (pin "3") (pinfunction "VBAT_3") (pintype "power_in"))
      (node (ref "V30") (pin "P1") (pinfunction "N_P1") (pintype "bidirectional"))
      (node (ref "V31") (pin "P1") (pinfunction "N_P1") (pintype "bidirectional"))
      (node (ref "V32") (pin "P1") (pinfunction "N_P1") (pintype "bidirectional"))
      (node (ref "V33") (pin "P1") (pinfunction "N_P1") (pintype "bidirectional"))
      (node (ref "V34") (pin "P1") (pinfunction "N_P1") (pintype "bidirectional"))
      (node (ref "V36") (pin "P1") (pinfunction "N_P1") (pintype "bidirectional"))
      (node (ref "V6") (pin "P1") (pinfunction "N_P1") (pintype "bidirectional"))
    )
    (net (code "43") (name "Net-(S2-C)") (class "Default")
      (node (ref "S2") (pin "2") (pinfunction "C_2") (pintype "bidirectional"))
      (node (ref "U5") (pin "12") (pinfunction "2S_12") (pintype "bidirectional"))
      (node (ref "U5") (pin "4") (pinfunction "1S_4") (pintype "bidirectional"))
    )
    (net (code "44") (name "Net-(U4-AVDD)") (class "Default")
      (node (ref "C13") (pin "1") (pinfunction "1_1") (pintype "passive"))
      (node (ref "U4") (pin "60") (pinfunction "AVDD_60") (pintype "bidirectional"))
    )
    (net (code "45") (name "Net-(U4-PG0(DIG3))") (class "Default")
      (node (ref "D6") (pin "A2") (pinfunction "A2_A2") (pintype "passive"))
      (node (ref "U4") (pin "14") (pinfunction "PG0(DIG3)_14") (pintype "bidirectional"))
    )
    (net (code "46") (name "Net-(U4-PG1(DIG1))") (class "Default")
      (node (ref "D6") (pin "A1") (pinfunction "A1_A1") (pintype "passive"))
      (node (ref "U4") (pin "15") (pinfunction "PG1(DIG1)_15") (pintype "bidirectional"))
    )
    (net (code "47") (name "Net-(U4-XTAL1)") (class "Default")
      (node (ref "C14") (pin "1") (pinfunction "1_1") (pintype "passive"))
      (node (ref "U4") (pin "57") (pinfunction "XTAL1_57") (pintype "bidirectional"))
      (node (ref "Y1") (pin "3") (pinfunction "2_3") (pintype "passive"))
    )
    (net (code "48") (name "Net-(U4-XTAL2)") (class "Default")
      (node (ref "C15") (pin "1") (pinfunction "1_1") (pintype "passive"))
      (node (ref "U4") (pin "56") (pinfunction "XTAL2_56") (pintype "bidirectional"))
      (node (ref "Y1") (pin "1") (pinfunction "1_1") (pintype "passive"))
    )
    (net (code "49") (name "PITCH") (class "Default")
      (node (ref "J3") (pin "V") (pinfunction "V_V") (pintype "bidirectional"))
      (node (ref "J8") (pin "V") (pinfunction "V_V") (pintype "bidirectional"))
      (node (ref "U4") (pin "2") (pinfunction "PF3(ADC3/DIG4)_2") (pintype "bidirectional"))
    )
    (net (code "50") (name "RESET") (class "Default")
      (node (ref "B1") (pin "1") (pinfunction "1_1") (pintype "passive"))
      (node (ref "B1") (pin "2") (pinfunction "1_2") (pintype "passive"))
      (node (ref "C1") (pin "1") (pinfunction "1_1") (pintype "passive"))
      (node (ref "J4") (pin "5") (pinfunction "5_5") (pintype "passive"))
      (node (ref "R3") (pin "1") (pinfunction "1_1") (pintype "passive"))
      (node (ref "U4") (pin "12") (pinfunction "RSTN_12") (pintype "bidirectional"))
    )
    (net (code "51") (name "RF") (class "Default")
      (node (ref "D4") (pin "A2") (pinfunction "A2_A2") (pintype "passive"))
      (node (ref "U4") (pin "16") (pinfunction "PG2(AMR)_16") (pintype "bidirectional"))
    )
    (net (code "52") (name "ROLL") (class "Default")
      (node (ref "J3") (pin "H") (pinfunction "H_H") (pintype "bidirectional"))
      (node (ref "J8") (pin "H") (pinfunction "H_H") (pintype "bidirectional"))
      (node (ref "U4") (pin "1") (pinfunction "PF2(ADC2/DIG2)_1") (pintype "bidirectional"))
    )
    (net (code "53") (name "RXI") (class "Default")
      (node (ref "U3") (pin "5") (pinfunction "RXD_5") (pintype "input"))
      (node (ref "U5") (pin "10") (pinfunction "3Z_10") (pintype "bidirectional"))
    )
    (net (code "54") (name "RXI-0") (class "Default")
      (node (ref "U4") (pin "47") (pinfunction "PE1(TXD0)_47") (pintype "bidirectional"))
      (node (ref "U5") (pin "11") (pinfunction "3Y0_11") (pintype "bidirectional"))
    )
    (net (code "55") (name "RXI-1") (class "Default")
      (node (ref "J5") (pin "RXI") (pinfunction "2_RXI") (pintype "passive"))
      (node (ref "J6") (pin "RXI") (pinfunction "1_RXI") (pintype "bidirectional"))
      (node (ref "U5") (pin "9") (pinfunction "3Y1_9") (pintype "bidirectional"))
    )
    (net (code "56") (name "RXLED") (class "Default")
      (node (ref "D5") (pin "C2") (pinfunction "C2_C2") (pintype "passive"))
      (node (ref "U3") (pin "22") (pinfunction "RXLED_22") (pintype "input"))
    )
    (net (code "57") (name "SCK") (class "Default")
      (node (ref "J4") (pin "3") (pinfunction "3_3") (pintype "passive"))
      (node (ref "U4") (pin "37") (pinfunction "PB1(SCK/PCINT1)_37") (pintype "bidirectional"))
    )
    (net (code "58") (name "SHIELD") (class "Default")
      (node (ref "B12") (pin "P2") (pinfunction "P2_P2") (pintype "bidirectional"))
    )
    (net (code "59") (name "THROTTLE") (class "Default")
      (node (ref "J2") (pin "V") (pinfunction "V_V") (pintype "bidirectional"))
      (node (ref "J7") (pin "V") (pinfunction "V_V") (pintype "bidirectional"))
      (node (ref "U4") (pin "64") (pinfunction "PF1(ADC1)_64") (pintype "bidirectional"))
    )
    (net (code "60") (name "TXLED") (class "Default")
      (node (ref "D5") (pin "C1") (pinfunction "C1_C1") (pintype "passive"))
      (node (ref "U3") (pin "23") (pinfunction "TXLED_23") (pintype "input"))
    )
    (net (code "61") (name "TXO") (class "Default")
      (node (ref "U3") (pin "1") (pinfunction "TXD_1") (pintype "output"))
      (node (ref "U5") (pin "6") (pinfunction "2Z_6") (pintype "bidirectional"))
    )
    (net (code "62") (name "TXO-0") (class "Default")
      (node (ref "U4") (pin "46") (pinfunction "PE0(RXD0/PCINT8)_46") (pintype "bidirectional"))
      (node (ref "U5") (pin "7") (pinfunction "2Y0_7") (pintype "bidirectional"))
    )
    (net (code "63") (name "TXO-1") (class "Default")
      (node (ref "J5") (pin "TXO") (pinfunction "3_TXO") (pintype "passive"))
      (node (ref "J6") (pin "TXO") (pinfunction "2_TXO") (pintype "bidirectional"))
      (node (ref "U5") (pin "5") (pinfunction "2Y1_5") (pintype "bidirectional"))
    )
    (net (code "64") (name "USB_D_N") (class "Default")
      (node (ref "J1") (pin "2") (pinfunction "2-D-_2") (pintype "bidirectional"))
      (node (ref "U3") (pin "16") (pinfunction "USBDM_16") (pintype "bidirectional"))
    )
    (net (code "65") (name "USB_D_P") (class "Default")
      (node (ref "J1") (pin "3") (pinfunction "3-D+_3") (pintype "bidirectional"))
      (node (ref "U3") (pin "15") (pinfunction "USBDP_15") (pintype "bidirectional"))
    )
    (net (code "66") (name "VBUS") (class "Default")
      (node (ref "C5") (pin "1") (pinfunction "1_1") (pintype "passive"))
      (node (ref "D1") (pin "A2") (pinfunction "A2_A2") (pintype "passive"))
      (node (ref "J1") (pin "1") (pinfunction "1-VCC_1") (pintype "bidirectional"))
      (node (ref "P1") (pin "T") (pinfunction "T_T") (pintype "bidirectional"))
      (node (ref "R3") (pin "5") (pinfunction "2_5") (pintype "passive"))
      (node (ref "S1") (pin "6") (pinfunction "C1_6") (pintype "bidirectional"))
      (node (ref "U2") (pin "4") (pinfunction "VDD_4") (pintype "power_in"))
      (node (ref "V1") (pin "P1") (pinfunction "N_P1") (pintype "bidirectional"))
      (node (ref "V2") (pin "P1") (pinfunction "N_P1") (pintype "bidirectional"))
      (node (ref "V23") (pin "P1") (pinfunction "N_P1") (pintype "bidirectional"))
      (node (ref "V24") (pin "P1") (pinfunction "N_P1") (pintype "bidirectional"))
      (node (ref "V26") (pin "P1") (pinfunction "N_P1") (pintype "bidirectional"))
      (node (ref "V27") (pin "P1") (pinfunction "N_P1") (pintype "bidirectional"))
      (node (ref "V28") (pin "P1") (pinfunction "N_P1") (pintype "bidirectional"))
    )
    (net (code "67") (name "VIN") (class "Default")
      (node (ref "C7") (pin "1") (pinfunction "1_1") (pintype "passive"))
      (node (ref "C8") (pin "1") (pinfunction "1_1") (pintype "passive"))
      (node (ref "D2") (pin "1") (pinfunction "C_1") (pintype "passive"))
      (node (ref "D3") (pin "1") (pinfunction "C_1") (pintype "passive"))
      (node (ref "J4") (pin "2") (pinfunction "2_2") (pintype "passive"))
      (node (ref "L1") (pin "RAW") (pinfunction "VIN_RAW") (pintype "bidirectional"))
      (node (ref "P2") (pin "T") (pinfunction "T_T") (pintype "bidirectional"))
      (node (ref "U3") (pin "20") (pinfunction "VCC_20") (pintype "power_in"))
    )
    (net (code "68") (name "YAW") (class "Default")
      (node (ref "J2") (pin "H") (pinfunction "H_H") (pintype "bidirectional"))
      (node (ref "J7") (pin "H") (pinfunction "H_H") (pintype "bidirectional"))
      (node (ref "U4") (pin "63") (pinfunction "PF0(ADC0)_63") (pintype "bidirectional"))
    )
    (net (code "69") (name "unconnected-(J1-4-ID-Pad4)") (class "Default")
      (node (ref "J1") (pin "4") (pinfunction "4-ID_4") (pintype "bidirectional"))
    )
    (net (code "70") (name "unconnected-(L1-PadSCK)") (class "Default")
      (node (ref "L1") (pin "SCK") (pinfunction "SCK_SCK") (pintype "bidirectional"))
    )
    (net (code "71") (name "unconnected-(L1-PadSDI)") (class "Default")
      (node (ref "L1") (pin "SDI") (pinfunction "SDI_SDI") (pintype "bidirectional"))
    )
    (net (code "72") (name "unconnected-(L1-PadSDO)") (class "Default")
      (node (ref "L1") (pin "SDO") (pinfunction "SDO_SDO") (pintype "bidirectional"))
    )
    (net (code "73") (name "unconnected-(L1-Pad{slash}CS)") (class "Default")
      (node (ref "L1") (pin "/CS") (pinfunction "/CS_/CS") (pintype "bidirectional"))
    )
    (net (code "74") (name "unconnected-(L1-SCL-PadCL)") (class "Default")
      (node (ref "L1") (pin "CL") (pinfunction "SCL_CL") (pintype "bidirectional"))
    )
    (net (code "75") (name "unconnected-(L1-SDA-PadDA)") (class "Default")
      (node (ref "L1") (pin "DA") (pinfunction "SDA_DA") (pintype "bidirectional"))
    )
    (net (code "76") (name "unconnected-(S1-OFF-Pad1)") (class "Default")
      (node (ref "S1") (pin "1") (pinfunction "OFF_1") (pintype "bidirectional"))
    )
    (net (code "77") (name "unconnected-(S1-OFF1-Pad5)") (class "Default")
      (node (ref "S1") (pin "5") (pinfunction "OFF1_5") (pintype "bidirectional"))
    )
    (net (code "78") (name "unconnected-(S2-C1-Pad6)") (class "Default")
      (node (ref "S2") (pin "6") (pinfunction "C1_6") (pintype "bidirectional"))
    )
    (net (code "79") (name "unconnected-(S2-OFF1-Pad5)") (class "Default")
      (node (ref "S2") (pin "5") (pinfunction "OFF1_5") (pintype "bidirectional"))
    )
    (net (code "80") (name "unconnected-(S2-ON1-Pad7)") (class "Default")
      (node (ref "S2") (pin "7") (pinfunction "ON1_7") (pintype "bidirectional"))
    )
    (net (code "81") (name "unconnected-(U3-DCD-Pad10)") (class "Default")
      (node (ref "U3") (pin "10") (pinfunction "DCD_10") (pintype "input"))
    )
    (net (code "82") (name "unconnected-(U3-DSR-Pad9)") (class "Default")
      (node (ref "U3") (pin "9") (pinfunction "DSR_9") (pintype "input"))
    )
    (net (code "83") (name "unconnected-(U3-OSCI-Pad27)") (class "Default")
      (node (ref "U3") (pin "27") (pinfunction "OSCI_27") (pintype "input"))
    )
    (net (code "84") (name "unconnected-(U3-OSCO-Pad28)") (class "Default")
      (node (ref "U3") (pin "28") (pinfunction "OSCO_28") (pintype "output"))
    )
    (net (code "85") (name "unconnected-(U3-PWREN-Pad14)") (class "Default")
      (node (ref "U3") (pin "14") (pinfunction "PWREN_14") (pintype "input"))
    )
    (net (code "86") (name "unconnected-(U3-RESET-Pad19)") (class "Default")
      (node (ref "U3") (pin "19") (pinfunction "RESET_19") (pintype "input"))
    )
    (net (code "87") (name "unconnected-(U3-RI-Pad6)") (class "Default")
      (node (ref "U3") (pin "6") (pinfunction "RI_6") (pintype "input"))
    )
    (net (code "88") (name "unconnected-(U3-RTS-Pad3)") (class "Default")
      (node (ref "U3") (pin "3") (pinfunction "RTS_3") (pintype "output"))
    )
    (net (code "89") (name "unconnected-(U3-SLEEP-Pad12)") (class "Default")
      (node (ref "U3") (pin "12") (pinfunction "SLEEP_12") (pintype "input"))
    )
    (net (code "90") (name "unconnected-(U3-TXDEN-Pad13)") (class "Default")
      (node (ref "U3") (pin "13") (pinfunction "TXDEN_13") (pintype "input"))
    )
    (net (code "91") (name "unconnected-(U4-AREF-Pad62)") (class "Default")
      (node (ref "U4") (pin "62") (pinfunction "AREF_62") (pintype "bidirectional"))
    )
    (net (code "92") (name "unconnected-(U4-PB0(SSN{slash}PCINT0)-Pad36)") (class "Default")
      (node (ref "U4") (pin "36") (pinfunction "PB0(SSN/PCINT0)_36") (pintype "bidirectional"))
    )
    (net (code "93") (name "unconnected-(U4-PB6(OC1B{slash}PCINT6)-Pad42)") (class "Default")
      (node (ref "U4") (pin "42") (pinfunction "PB6(OC1B/PCINT6)_42") (pintype "bidirectional"))
    )
    (net (code "94") (name "unconnected-(U4-PB7(OC0A{slash}OC1C{slash}PCINT7)-Pad43)") (class "Default")
      (node (ref "U4") (pin "43") (pinfunction "PB7(OC0A/OC1C/PCINT7)_43") (pintype "bidirectional"))
    )
    (net (code "95") (name "unconnected-(U4-PD4(ICP1)-Pad29)") (class "Default")
      (node (ref "U4") (pin "29") (pinfunction "PD4(ICP1)_29") (pintype "bidirectional"))
    )
    (net (code "96") (name "unconnected-(U4-PD5(XCK1)-Pad30)") (class "Default")
      (node (ref "U4") (pin "30") (pinfunction "PD5(XCK1)_30") (pintype "bidirectional"))
    )
    (net (code "97") (name "unconnected-(U4-PE2(XCK0{slash}AIN0)-Pad48)") (class "Default")
      (node (ref "U4") (pin "48") (pinfunction "PE2(XCK0/AIN0)_48") (pintype "bidirectional"))
    )
    (net (code "98") (name "unconnected-(U4-PE3(OC3A{slash}AIN1)-Pad49)") (class "Default")
      (node (ref "U4") (pin "49") (pinfunction "PE3(OC3A/AIN1)_49") (pintype "bidirectional"))
    )
    (net (code "99") (name "unconnected-(U4-PF4(ADC4{slash}TCK)-Pad3)") (class "Default")
      (node (ref "U4") (pin "3") (pinfunction "PF4(ADC4/TCK)_3") (pintype "bidirectional"))
    )
    (net (code "100") (name "unconnected-(U4-PF5(ADC5{slash}TMS)-Pad4)") (class "Default")
      (node (ref "U4") (pin "4") (pinfunction "PF5(ADC5/TMS)_4") (pintype "bidirectional"))
    )
    (net (code "101") (name "unconnected-(U4-PF6(ADC6{slash}TDO)-Pad5)") (class "Default")
      (node (ref "U4") (pin "5") (pinfunction "PF6(ADC6/TDO)_5") (pintype "bidirectional"))
    )
    (net (code "102") (name "unconnected-(U4-PG3(TOSC2)-Pad17)") (class "Default")
      (node (ref "U4") (pin "17") (pinfunction "PG3(TOSC2)_17") (pintype "bidirectional"))
    )
    (net (code "103") (name "unconnected-(U4-PG4(TOSC1)-Pad18)") (class "Default")
      (node (ref "U4") (pin "18") (pinfunction "PG4(TOSC1)_18") (pintype "bidirectional"))
    )
    (net (code "104") (name "unconnected-(U4-PG5(OC0B)-Pad19)") (class "Default")
      (node (ref "U4") (pin "19") (pinfunction "PG5(OC0B)_19") (pintype "bidirectional"))
    )
    (net (code "105") (name "unconnected-(U4-RSTON-Pad13)") (class "Default")
      (node (ref "U4") (pin "13") (pinfunction "RSTON_13") (pintype "bidirectional"))
    )
  )
)
